# Timer.net
KiCad netlist of a schematic drawn in EAGLE
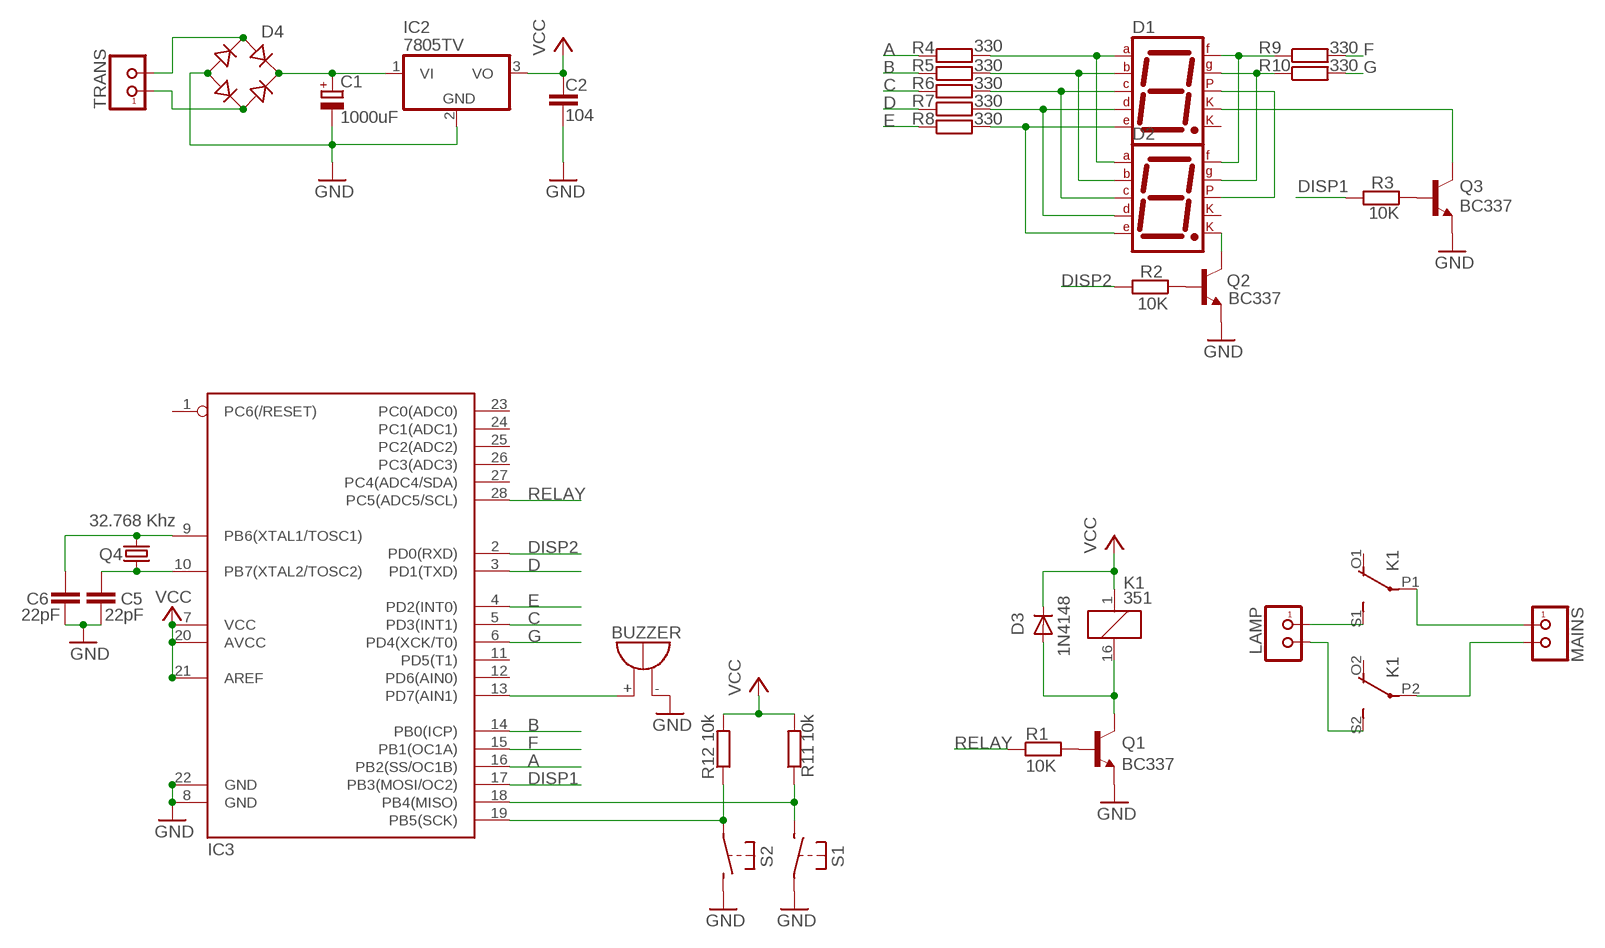
[diagram p0: schematic, sheet 1]

(export (version "E")
  (design (tool "Eeschema 10.0.6"))
  (components
    (comp (ref "BUZZER")
      (value "F/HMB")
      (footprint "eagle-import:F_HMB")
      (libsource (lib "eagle-import") (part "F/HMB"))
    )
    (comp (ref "C1")
      (value "1000uF")
      (footprint "eagle-import:C-TT2D13-SIDE")
      (libsource (lib "eagle-import") (part "C-POL13-SIDE"))
    )
    (comp (ref "C2")
      (value "104")
      (footprint "eagle-import:C-22X6(FAKI)")
      (libsource (lib "eagle-import") (part "CC-22X6(FAKI)"))
    )
    (comp (ref "C5")
      (value "22pF")
      (footprint "eagle-import:C-22X6(FAKI)")
      (libsource (lib "eagle-import") (part "CC-22X6(FAKI)"))
    )
    (comp (ref "C6")
      (value "22pF")
      (footprint "eagle-import:C-22X6(FAKI)")
      (libsource (lib "eagle-import") (part "CC-22X6(FAKI)"))
    )
    (comp (ref "D1")
      (value "7SEG-CK")
      (footprint "eagle-import:7SEG-13")
      (libsource (lib "eagle-import") (part "7SEG-CK"))
    )
    (comp (ref "D2")
      (value "7SEG-CK")
      (footprint "eagle-import:7SEG-13")
      (libsource (lib "eagle-import") (part "7SEG-CK"))
    )
    (comp (ref "D3")
      (value "1N4148")
      (footprint "eagle-import:DO35-10")
      (libsource (lib "eagle-import") (part "1N4148DO35-10"))
    )
    (comp (ref "D4")
      (value "RECTIFIER-1A")
      (footprint "eagle-import:RECTIFIER-1A")
      (libsource (lib "eagle-import") (part "RECTIFIER-1A"))
    )
    (comp (ref "IC2")
      (value "7805TV")
      (footprint "eagle-import:TO220V")
      (libsource (lib "eagle-import") (part "78TV05"))
    )
    (comp (ref "IC3")
      (value "ATMEGA-8-P")
      (footprint "eagle-import:DIL28-3")
      (libsource (lib "eagle-import") (part "ATMEGA-8-P"))
    )
    (comp (ref "K1")
      (value "351")
      (footprint "eagle-import:351")
      (libsource (lib "eagle-import") (part "351"))
    )
    (comp (ref "LAMP")
      (value "KLEMESX2")
      (footprint "eagle-import:KLEMESX2")
      (libsource (lib "eagle-import") (part "KLEMESX2"))
    )
    (comp (ref "MAINS")
      (value "KLEMESX2")
      (footprint "eagle-import:KLEMESX2")
      (libsource (lib "eagle-import") (part "KLEMESX2"))
    )
    (comp (ref "Q1")
      (value "BC337")
      (footprint "eagle-import:TO92-EBC")
      (libsource (lib "eagle-import") (part "BC548"))
    )
    (comp (ref "Q2")
      (value "BC337")
      (footprint "eagle-import:TO92-EBC")
      (libsource (lib "eagle-import") (part "BC548"))
    )
    (comp (ref "Q3")
      (value "BC337")
      (footprint "eagle-import:TO92-EBC")
      (libsource (lib "eagle-import") (part "BC548"))
    )
    (comp (ref "Q4")
      (value "32.768 Khz")
      (footprint "eagle-import:TC38")
      (libsource (lib "eagle-import") (part "CRYSTALTC38"))
    )
    (comp (ref "R1")
      (value "10K")
      (footprint "eagle-import:R0270_10")
      (libsource (lib "eagle-import") (part "R0207/10"))
    )
    (comp (ref "R2")
      (value "10K")
      (footprint "eagle-import:R0270_10")
      (libsource (lib "eagle-import") (part "R0207/10"))
    )
    (comp (ref "R3")
      (value "10K")
      (footprint "eagle-import:R0270_10")
      (libsource (lib "eagle-import") (part "R0207/10"))
    )
    (comp (ref "R4")
      (value "330")
      (footprint "eagle-import:R0270_10")
      (libsource (lib "eagle-import") (part "R0207/10"))
    )
    (comp (ref "R5")
      (value "330")
      (footprint "eagle-import:R0270_10")
      (libsource (lib "eagle-import") (part "R0207/10"))
    )
    (comp (ref "R6")
      (value "330")
      (footprint "eagle-import:R0270_10")
      (libsource (lib "eagle-import") (part "R0207/10"))
    )
    (comp (ref "R7")
      (value "330")
      (footprint "eagle-import:R0270_10")
      (libsource (lib "eagle-import") (part "R0207/10"))
    )
    (comp (ref "R8")
      (value "330")
      (footprint "eagle-import:R0270_10")
      (libsource (lib "eagle-import") (part "R0207/10"))
    )
    (comp (ref "R9")
      (value "330")
      (footprint "eagle-import:R0270_10")
      (libsource (lib "eagle-import") (part "R0207/10"))
    )
    (comp (ref "R10")
      (value "330")
      (footprint "eagle-import:R0270_10")
      (libsource (lib "eagle-import") (part "R0207/10"))
    )
    (comp (ref "R11")
      (value "10k")
      (footprint "eagle-import:R0270_10")
      (libsource (lib "eagle-import") (part "R0207/10"))
    )
    (comp (ref "R12")
      (value "10k")
      (footprint "eagle-import:R0270_10")
      (libsource (lib "eagle-import") (part "R0207/10"))
    )
    (comp (ref "S1")
      (value "SWITCH")
      (footprint "eagle-import:SW-BT")
      (libsource (lib "eagle-import") (part "SWITCH"))
    )
    (comp (ref "S2")
      (value "SWITCH")
      (footprint "eagle-import:SW-BT")
      (libsource (lib "eagle-import") (part "SWITCH"))
    )
    (comp (ref "TRANS")
      (value "KLEMESX2")
      (footprint "eagle-import:KLEMESX2")
      (libsource (lib "eagle-import") (part "KLEMESX2"))
    )
  )
  (nets
    (net (code "1") (name "/A") (class "Default")
      (node (ref "IC3") (pin "16") (pinfunction "PB2(SS/OC1B)_16") (pintype "bidirectional"))
      (node (ref "R4") (pin "1") (pinfunction "1_1") (pintype "passive"))
    )
    (net (code "2") (name "/B") (class "Default")
      (node (ref "IC3") (pin "14") (pinfunction "PB0(ICP)_14") (pintype "bidirectional"))
      (node (ref "R5") (pin "1") (pinfunction "1_1") (pintype "passive"))
    )
    (net (code "3") (name "/C") (class "Default")
      (node (ref "IC3") (pin "5") (pinfunction "PD3(INT1)_5") (pintype "bidirectional"))
      (node (ref "R6") (pin "1") (pinfunction "1_1") (pintype "passive"))
    )
    (net (code "4") (name "/D") (class "Default")
      (node (ref "IC3") (pin "3") (pinfunction "PD1(TXD)_3") (pintype "bidirectional"))
      (node (ref "R7") (pin "1") (pinfunction "1_1") (pintype "passive"))
    )
    (net (code "5") (name "/DISP1") (class "Default")
      (node (ref "IC3") (pin "17") (pinfunction "PB3(MOSI/OC2)_17") (pintype "bidirectional"))
      (node (ref "R3") (pin "2") (pinfunction "2_2") (pintype "passive"))
    )
    (net (code "6") (name "/DISP2") (class "Default")
      (node (ref "IC3") (pin "2") (pinfunction "PD0(RXD)_2") (pintype "bidirectional"))
      (node (ref "R2") (pin "2") (pinfunction "2_2") (pintype "passive"))
    )
    (net (code "7") (name "/E") (class "Default")
      (node (ref "IC3") (pin "4") (pinfunction "PD2(INT0)_4") (pintype "bidirectional"))
      (node (ref "R8") (pin "1") (pinfunction "1_1") (pintype "passive"))
    )
    (net (code "8") (name "/F") (class "Default")
      (node (ref "IC3") (pin "15") (pinfunction "PB1(OC1A)_15") (pintype "bidirectional"))
      (node (ref "R9") (pin "2") (pinfunction "2_2") (pintype "passive"))
    )
    (net (code "9") (name "/G") (class "Default")
      (node (ref "IC3") (pin "6") (pinfunction "PD4(XCK/T0)_6") (pintype "bidirectional"))
      (node (ref "R10") (pin "2") (pinfunction "2_2") (pintype "passive"))
    )
    (net (code "10") (name "/RELAY") (class "Default")
      (node (ref "IC3") (pin "28") (pinfunction "PC5(ADC5/SCL)_28") (pintype "bidirectional"))
      (node (ref "R1") (pin "1") (pinfunction "1_1") (pintype "passive"))
    )
    (net (code "11") (name "GND") (class "Default")
      (node (ref "BUZZER") (pin "-") (pinfunction "-_-") (pintype "passive"))
      (node (ref "C1") (pin "-") (pinfunction "-_-") (pintype "passive"))
      (node (ref "C2") (pin "2") (pinfunction "2_2") (pintype "passive"))
      (node (ref "C5") (pin "2") (pinfunction "2_2") (pintype "passive"))
      (node (ref "C6") (pin "2") (pinfunction "2_2") (pintype "passive"))
      (node (ref "D4") (pin "-") (pinfunction "-_-") (pintype "passive"))
      (node (ref "IC2") (pin "2") (pinfunction "GND_2") (pintype "passive"))
      (node (ref "IC3") (pin "22") (pinfunction "GND_22") (pintype "power_in"))
      (node (ref "IC3") (pin "8") (pinfunction "GND_8") (pintype "power_in"))
      (node (ref "Q1") (pin "E") (pinfunction "E_E") (pintype "passive"))
      (node (ref "Q2") (pin "E") (pinfunction "E_E") (pintype "passive"))
      (node (ref "Q3") (pin "E") (pinfunction "E_E") (pintype "passive"))
      (node (ref "S1") (pin "P$1") (pinfunction "P_P$1") (pintype "passive"))
      (node (ref "S2") (pin "P$2") (pinfunction "S_P$2") (pintype "passive"))
    )
    (net (code "12") (name "Net-(D1-A)") (class "Default")
      (node (ref "D1") (pin "7") (pinfunction "A_7") (pintype "passive"))
      (node (ref "D2") (pin "7") (pinfunction "A_7") (pintype "passive"))
      (node (ref "R4") (pin "2") (pinfunction "2_2") (pintype "passive"))
    )
    (net (code "13") (name "Net-(D1-B)") (class "Default")
      (node (ref "D1") (pin "6") (pinfunction "B_6") (pintype "passive"))
      (node (ref "D2") (pin "6") (pinfunction "B_6") (pintype "passive"))
      (node (ref "R5") (pin "2") (pinfunction "2_2") (pintype "passive"))
    )
    (net (code "14") (name "Net-(D1-C)") (class "Default")
      (node (ref "D1") (pin "4") (pinfunction "C_4") (pintype "passive"))
      (node (ref "D2") (pin "4") (pinfunction "C_4") (pintype "passive"))
      (node (ref "R6") (pin "2") (pinfunction "2_2") (pintype "passive"))
    )
    (net (code "15") (name "Net-(D1-CK1)") (class "Default")
      (node (ref "D1") (pin "3") (pinfunction "CK1_3") (pintype "passive"))
      (node (ref "Q3") (pin "C") (pinfunction "C_C") (pintype "passive"))
    )
    (net (code "16") (name "Net-(D1-D)") (class "Default")
      (node (ref "D1") (pin "2") (pinfunction "D_2") (pintype "passive"))
      (node (ref "D2") (pin "2") (pinfunction "D_2") (pintype "passive"))
      (node (ref "R7") (pin "2") (pinfunction "2_2") (pintype "passive"))
    )
    (net (code "17") (name "Net-(D1-DP)") (class "Default")
      (node (ref "D1") (pin "5") (pinfunction "DP_5") (pintype "passive"))
      (node (ref "D2") (pin "5") (pinfunction "DP_5") (pintype "passive"))
    )
    (net (code "18") (name "Net-(D1-E)") (class "Default")
      (node (ref "D1") (pin "1") (pinfunction "E_1") (pintype "passive"))
      (node (ref "D2") (pin "1") (pinfunction "E_1") (pintype "passive"))
      (node (ref "R8") (pin "2") (pinfunction "2_2") (pintype "passive"))
    )
    (net (code "19") (name "Net-(D1-F)") (class "Default")
      (node (ref "D1") (pin "9") (pinfunction "F_9") (pintype "passive"))
      (node (ref "D2") (pin "9") (pinfunction "F_9") (pintype "passive"))
      (node (ref "R9") (pin "1") (pinfunction "1_1") (pintype "passive"))
    )
    (net (code "20") (name "Net-(D1-G)") (class "Default")
      (node (ref "D1") (pin "10") (pinfunction "G_10") (pintype "passive"))
      (node (ref "D2") (pin "10") (pinfunction "G_10") (pintype "passive"))
      (node (ref "R10") (pin "1") (pinfunction "1_1") (pintype "passive"))
    )
    (net (code "21") (name "Net-(D2-CK2)") (class "Default")
      (node (ref "D2") (pin "8") (pinfunction "CK2_8") (pintype "passive"))
      (node (ref "Q2") (pin "C") (pinfunction "C_C") (pintype "passive"))
    )
    (net (code "22") (name "Net-(D4-PadAC1)") (class "Default")
      (node (ref "D4") (pin "AC1") (pinfunction "AC1_AC1") (pintype "passive"))
      (node (ref "TRANS") (pin "2") (pinfunction "2_2") (pintype "passive"))
    )
    (net (code "23") (name "Net-(D4-PadAC2)") (class "Default")
      (node (ref "D4") (pin "AC2") (pinfunction "AC2_AC2") (pintype "passive"))
      (node (ref "TRANS") (pin "1") (pinfunction "1_1") (pintype "passive"))
    )
    (net (code "24") (name "Net-(IC2-VI)") (class "Default")
      (node (ref "C1") (pin "+") (pinfunction "+_+") (pintype "passive"))
      (node (ref "D4") (pin "+") (pinfunction "+_+") (pintype "passive"))
      (node (ref "IC2") (pin "1") (pinfunction "VI_1") (pintype "input"))
    )
    (net (code "25") (name "Net-(IC3-PB4(MISO))") (class "Default")
      (node (ref "IC3") (pin "18") (pinfunction "PB4(MISO)_18") (pintype "bidirectional"))
      (node (ref "R11") (pin "1") (pinfunction "1_1") (pintype "passive"))
      (node (ref "S1") (pin "P$2") (pinfunction "S_P$2") (pintype "passive"))
    )
    (net (code "26") (name "Net-(IC3-PB5(SCK))") (class "Default")
      (node (ref "IC3") (pin "19") (pinfunction "PB5(SCK)_19") (pintype "bidirectional"))
      (node (ref "R12") (pin "1") (pinfunction "1_1") (pintype "passive"))
      (node (ref "S2") (pin "P$1") (pinfunction "P_P$1") (pintype "passive"))
    )
    (net (code "27") (name "Net-(IC3-PB6(XTAL1{slash}TOSC1))") (class "Default")
      (node (ref "C6") (pin "1") (pinfunction "1_1") (pintype "passive"))
      (node (ref "IC3") (pin "9") (pinfunction "PB6(XTAL1/TOSC1)_9") (pintype "bidirectional"))
      (node (ref "Q4") (pin "2") (pinfunction "2_2") (pintype "passive"))
    )
    (net (code "28") (name "Net-(IC3-PB7(XTAL2{slash}TOSC2))") (class "Default")
      (node (ref "C5") (pin "1") (pinfunction "1_1") (pintype "passive"))
      (node (ref "IC3") (pin "10") (pinfunction "PB7(XTAL2/TOSC2)_10") (pintype "bidirectional"))
      (node (ref "Q4") (pin "1") (pinfunction "1_1") (pintype "passive"))
    )
    (net (code "29") (name "Net-(IC3-PD7(AIN1))") (class "Default")
      (node (ref "BUZZER") (pin "+") (pinfunction "+_+") (pintype "passive"))
      (node (ref "IC3") (pin "13") (pinfunction "PD7(AIN1)_13") (pintype "bidirectional"))
    )
    (net (code "30") (name "Net-(K1A-2)") (class "Default")
      (node (ref "D3") (pin "A") (pinfunction "A_A") (pintype "passive"))
      (node (ref "K1") (pin "16") (pinfunction "2_16") (pintype "passive"))
      (node (ref "Q1") (pin "C") (pinfunction "C_C") (pintype "passive"))
    )
    (net (code "31") (name "Net-(K1B-P)") (class "Default")
      (node (ref "K1") (pin "P1") (pinfunction "P_P1") (pintype "passive"))
      (node (ref "MAINS") (pin "1") (pinfunction "1_1") (pintype "passive"))
    )
    (net (code "32") (name "Net-(K1B-S)") (class "Default")
      (node (ref "K1") (pin "S1") (pinfunction "S_S1") (pintype "passive"))
      (node (ref "LAMP") (pin "1") (pinfunction "1_1") (pintype "passive"))
    )
    (net (code "33") (name "Net-(K1C-P)") (class "Default")
      (node (ref "K1") (pin "P2") (pinfunction "P_P2") (pintype "passive"))
      (node (ref "MAINS") (pin "2") (pinfunction "2_2") (pintype "passive"))
    )
    (net (code "34") (name "Net-(K1C-S)") (class "Default")
      (node (ref "K1") (pin "S2") (pinfunction "S_S2") (pintype "passive"))
      (node (ref "LAMP") (pin "2") (pinfunction "2_2") (pintype "passive"))
    )
    (net (code "35") (name "Net-(Q1-PadB)") (class "Default")
      (node (ref "Q1") (pin "B") (pinfunction "B_B") (pintype "passive"))
      (node (ref "R1") (pin "2") (pinfunction "2_2") (pintype "passive"))
    )
    (net (code "36") (name "Net-(Q2-PadB)") (class "Default")
      (node (ref "Q2") (pin "B") (pinfunction "B_B") (pintype "passive"))
      (node (ref "R2") (pin "1") (pinfunction "1_1") (pintype "passive"))
    )
    (net (code "37") (name "Net-(Q3-PadB)") (class "Default")
      (node (ref "Q3") (pin "B") (pinfunction "B_B") (pintype "passive"))
      (node (ref "R3") (pin "1") (pinfunction "1_1") (pintype "passive"))
    )
    (net (code "38") (name "VCC") (class "Default")
      (node (ref "C2") (pin "1") (pinfunction "1_1") (pintype "passive"))
      (node (ref "D3") (pin "C") (pinfunction "C_C") (pintype "passive"))
      (node (ref "IC2") (pin "3") (pinfunction "VO_3") (pintype "passive"))
      (node (ref "IC3") (pin "20") (pinfunction "AVCC_20") (pintype "power_in"))
      (node (ref "IC3") (pin "21") (pinfunction "AREF_21") (pintype "passive"))
      (node (ref "IC3") (pin "7") (pinfunction "VCC_7") (pintype "power_in"))
      (node (ref "K1") (pin "1") (pinfunction "1_1") (pintype "passive"))
      (node (ref "R11") (pin "2") (pinfunction "2_2") (pintype "passive"))
      (node (ref "R12") (pin "2") (pinfunction "2_2") (pintype "passive"))
    )
    (net (code "39") (name "unconnected-(D1-CK2-Pad8)") (class "Default")
      (node (ref "D1") (pin "8") (pinfunction "CK2_8") (pintype "passive"))
    )
    (net (code "40") (name "unconnected-(D2-CK1-Pad3)") (class "Default")
      (node (ref "D2") (pin "3") (pinfunction "CK1_3") (pintype "passive"))
    )
    (net (code "41") (name "unconnected-(IC3-PC0(ADC0)-Pad23)") (class "Default")
      (node (ref "IC3") (pin "23") (pinfunction "PC0(ADC0)_23") (pintype "bidirectional"))
    )
    (net (code "42") (name "unconnected-(IC3-PC1(ADC1)-Pad24)") (class "Default")
      (node (ref "IC3") (pin "24") (pinfunction "PC1(ADC1)_24") (pintype "bidirectional"))
    )
    (net (code "43") (name "unconnected-(IC3-PC2(ADC2)-Pad25)") (class "Default")
      (node (ref "IC3") (pin "25") (pinfunction "PC2(ADC2)_25") (pintype "bidirectional"))
    )
    (net (code "44") (name "unconnected-(IC3-PC3(ADC3)-Pad26)") (class "Default")
      (node (ref "IC3") (pin "26") (pinfunction "PC3(ADC3)_26") (pintype "bidirectional"))
    )
    (net (code "45") (name "unconnected-(IC3-PC4(ADC4{slash}SDA)-Pad27)") (class "Default")
      (node (ref "IC3") (pin "27") (pinfunction "PC4(ADC4/SDA)_27") (pintype "bidirectional"))
    )
    (net (code "46") (name "unconnected-(IC3-PC6({slash}RESET)-Pad1)") (class "Default")
      (node (ref "IC3") (pin "1") (pinfunction "PC6(/RESET)_1") (pintype "bidirectional"))
    )
    (net (code "47") (name "unconnected-(IC3-PD5(T1)-Pad11)") (class "Default")
      (node (ref "IC3") (pin "11") (pinfunction "PD5(T1)_11") (pintype "bidirectional"))
    )
    (net (code "48") (name "unconnected-(IC3-PD6(AIN0)-Pad12)") (class "Default")
      (node (ref "IC3") (pin "12") (pinfunction "PD6(AIN0)_12") (pintype "bidirectional"))
    )
    (net (code "49") (name "unconnected-(K1B-O-PadO1)") (class "Default")
      (node (ref "K1") (pin "O1") (pinfunction "O_O1") (pintype "passive"))
    )
    (net (code "50") (name "unconnected-(K1C-O-PadO2)") (class "Default")
      (node (ref "K1") (pin "O2") (pinfunction "O_O2") (pintype "passive"))
    )
  )
)
